# cvtv.net
KiCad netlist of a schematic drawn in EAGLE
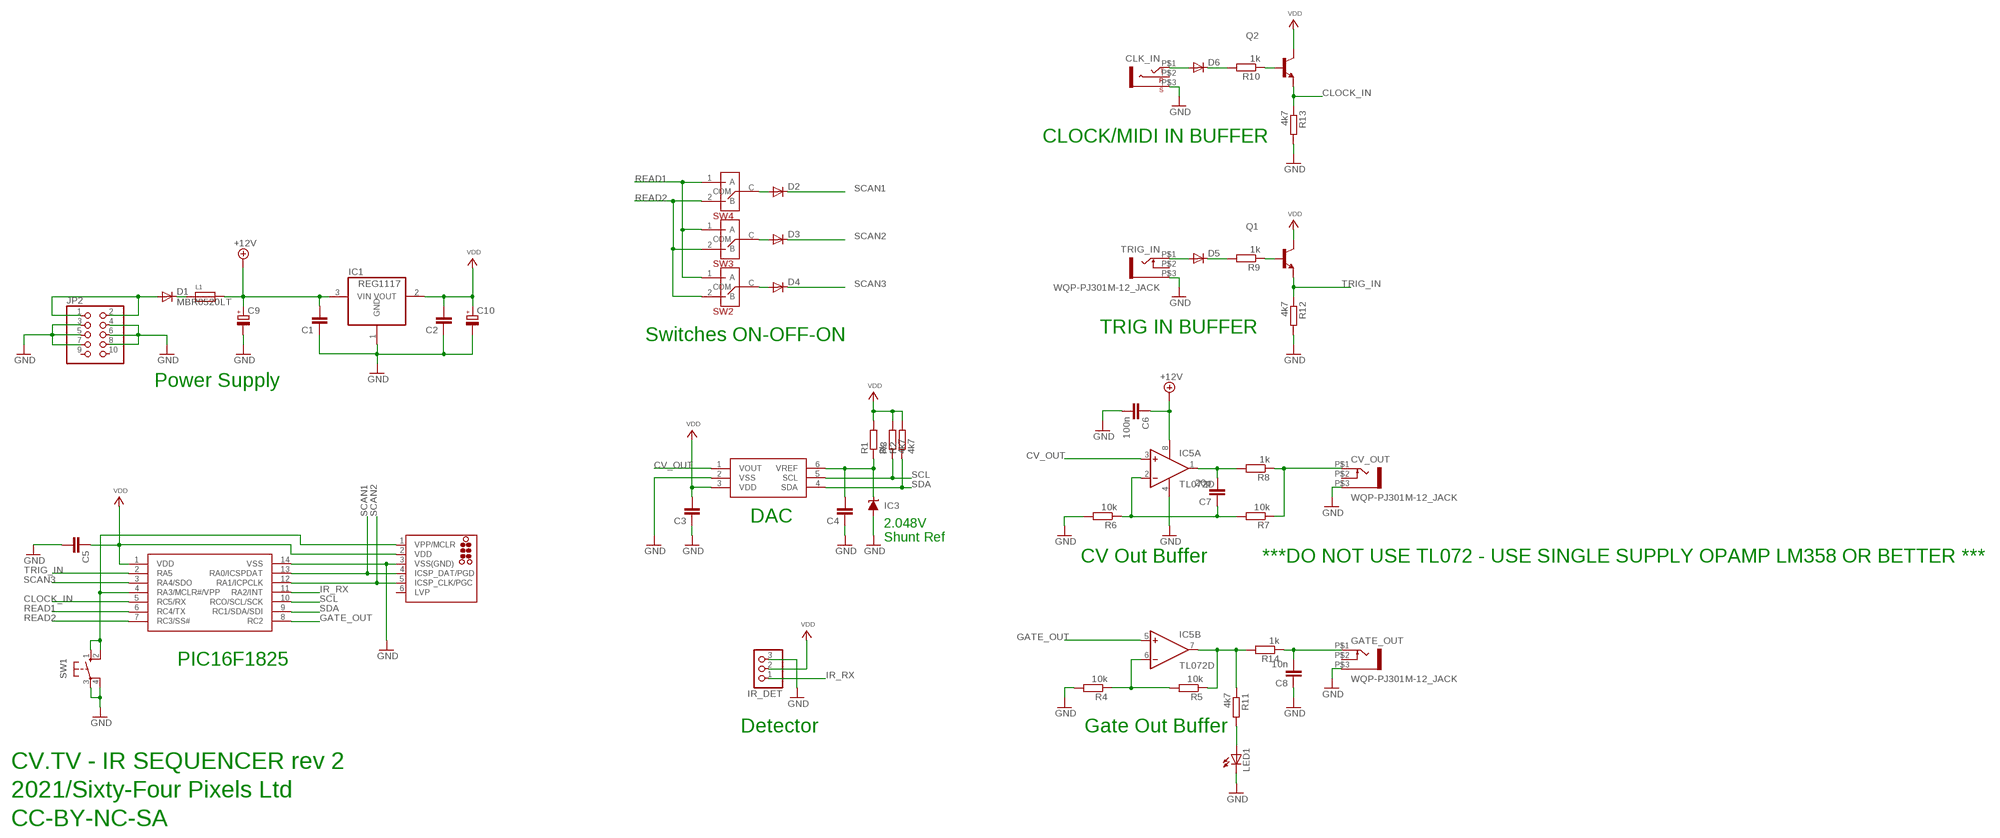
[diagram p0: schematic, sheet 1]

(export (version "E")
  (design (tool "Eeschema 10.0.6"))
  (components
    (comp (ref "C1")
      (value "C-EUC0805")
      (footprint "eagle-import:C0805")
      (libsource (lib "eagle-import") (part "C-EUC0805"))
    )
    (comp (ref "C2")
      (value "C-EUC0805")
      (footprint "eagle-import:C0805")
      (libsource (lib "eagle-import") (part "C-EUC0805"))
    )
    (comp (ref "C3")
      (value "C-EUC0805")
      (footprint "eagle-import:C0805")
      (libsource (lib "eagle-import") (part "C-EUC0805"))
    )
    (comp (ref "C4")
      (value "C-EUC0805")
      (footprint "eagle-import:C0805")
      (libsource (lib "eagle-import") (part "C-EUC0805"))
    )
    (comp (ref "C5")
      (value "C-EUC0805")
      (footprint "eagle-import:C0805")
      (libsource (lib "eagle-import") (part "C-EUC0805"))
    )
    (comp (ref "C6")
      (value "100n")
      (footprint "eagle-import:C0805")
      (libsource (lib "eagle-import") (part "C-EUC0805"))
    )
    (comp (ref "C7")
      (value "20p")
      (footprint "eagle-import:C0805")
      (libsource (lib "eagle-import") (part "C-EUC0805"))
    )
    (comp (ref "C8")
      (value "10n")
      (footprint "eagle-import:C0805")
      (libsource (lib "eagle-import") (part "C-EUC0805"))
    )
    (comp (ref "C9")
      (value "CPOL-EUE2-5")
      (footprint "eagle-import:E2-5")
      (libsource (lib "eagle-import") (part "CPOL-EUE2-5"))
    )
    (comp (ref "C10")
      (value "CPOL-EUE2-5")
      (footprint "eagle-import:E2-5")
      (libsource (lib "eagle-import") (part "CPOL-EUE2-5"))
    )
    (comp (ref "CLK_IN")
      (value "THONKICONN_STEREO")
      (footprint "eagle-import:WQP-PJ301M-ST")
      (libsource (lib "eagle-import") (part "THONKICONN_STEREO"))
    )
    (comp (ref "CV_OUT")
      (value "WQP-PJ301M-12_JACK")
      (footprint "eagle-import:WQP-PJ301M-12_JACK")
      (libsource (lib "eagle-import") (part "WQP-PJ301M-12_JACK"))
    )
    (comp (ref "D1")
      (value "MBR0520LT")
      (footprint "eagle-import:SOD123")
      (libsource (lib "eagle-import") (part "MBR0520LT"))
    )
    (comp (ref "D2")
      (value "TS4148")
      (footprint "eagle-import:D0805")
      (libsource (lib "eagle-import") (part "TS4148"))
    )
    (comp (ref "D3")
      (value "TS4148")
      (footprint "eagle-import:D0805")
      (libsource (lib "eagle-import") (part "TS4148"))
    )
    (comp (ref "D4")
      (value "TS4148")
      (footprint "eagle-import:D0805")
      (libsource (lib "eagle-import") (part "TS4148"))
    )
    (comp (ref "D5")
      (value "TS4148")
      (footprint "eagle-import:D0805")
      (libsource (lib "eagle-import") (part "TS4148"))
    )
    (comp (ref "D6")
      (value "TS4148")
      (footprint "eagle-import:D0805")
      (libsource (lib "eagle-import") (part "TS4148"))
    )
    (comp (ref "GATE_OUT")
      (value "WQP-PJ301M-12_JACK")
      (footprint "eagle-import:WQP-PJ301M-12_JACK")
      (libsource (lib "eagle-import") (part "WQP-PJ301M-12_JACK"))
    )
    (comp (ref "IC1")
      (value "REG1117")
      (footprint "eagle-import:SOT223")
      (libsource (lib "eagle-import") (part "REG1117"))
    )
    (comp (ref "IC2")
      (value "PIC16F1825SO14")
      (footprint "eagle-import:SO14")
      (libsource (lib "eagle-import") (part "PIC16F1825SO14"))
    )
    (comp (ref "IC3")
      (value "LM4041A12DBZ")
      (footprint "eagle-import:DBZ_R-PDSO-G3")
      (fields (field (name "MPN") "LM4041A12IDBZR"))
      (libsource (lib "eagle-import") (part "LM4041DBZA12"))
    )
    (comp (ref "IC4")
      (value "MCP4726")
      (footprint "eagle-import:SOT23-6")
      (libsource (lib "eagle-import") (part "MCP4726"))
    )
    (comp (ref "IC5")
      (value "TL072D")
      (footprint "eagle-import:SO08")
      (libsource (lib "eagle-import") (part "TL072D"))
    )
    (comp (ref "ICSP")
      (value "TC2030-MCP-NL")
      (footprint "eagle-import:TC2030-MCP-NL")
      (libsource (lib "eagle-import") (part "TC2030-MCP-NL"))
    )
    (comp (ref "IR_DET")
      (value "PINHD-1X3")
      (footprint "eagle-import:1X03")
      (libsource (lib "eagle-import") (part "PINHD-1X3"))
    )
    (comp (ref "JP2")
      (value "PINHD-2X5")
      (footprint "eagle-import:2X05")
      (libsource (lib "eagle-import") (part "PINHD-2X5"))
    )
    (comp (ref "L1")
      (value "FERRITE")
      (footprint "eagle-import:0603")
      (libsource (lib "eagle-import") (part "FERRITE"))
    )
    (comp (ref "LED1")
      (value "LED3MM")
      (footprint "eagle-import:LED3MM")
      (libsource (lib "eagle-import") (part "LED3MM"))
    )
    (comp (ref "Q1")
      (value "MMBT3904LT1-NPN-SOT23-BEC")
      (footprint "eagle-import:SOT23-BEC")
      (libsource (lib "eagle-import") (part "-NPN-SOT23-BECMMBT3904LT1"))
    )
    (comp (ref "Q2")
      (value "MMBT3904LT1-NPN-SOT23-BEC")
      (footprint "eagle-import:SOT23-BEC")
      (libsource (lib "eagle-import") (part "-NPN-SOT23-BECMMBT3904LT1"))
    )
    (comp (ref "R1")
      (value "3k")
      (footprint "eagle-import:R0805")
      (libsource (lib "eagle-import") (part "R-EU_R0805"))
    )
    (comp (ref "R2")
      (value "4k7")
      (footprint "eagle-import:R0805")
      (libsource (lib "eagle-import") (part "R-EU_R0805"))
    )
    (comp (ref "R3")
      (value "4k7")
      (footprint "eagle-import:R0805")
      (libsource (lib "eagle-import") (part "R-EU_R0805"))
    )
    (comp (ref "R4")
      (value "10k")
      (footprint "eagle-import:R0805")
      (libsource (lib "eagle-import") (part "R-EU_R0805"))
    )
    (comp (ref "R5")
      (value "10k")
      (footprint "eagle-import:R0805")
      (libsource (lib "eagle-import") (part "R-EU_R0805"))
    )
    (comp (ref "R6")
      (value "10k")
      (footprint "eagle-import:R0805")
      (libsource (lib "eagle-import") (part "R-EU_R0805"))
    )
    (comp (ref "R7")
      (value "10k")
      (footprint "eagle-import:R0805")
      (libsource (lib "eagle-import") (part "R-EU_R0805"))
    )
    (comp (ref "R8")
      (value "1k")
      (footprint "eagle-import:R0805")
      (libsource (lib "eagle-import") (part "R-EU_R0805"))
    )
    (comp (ref "R9")
      (value "1k")
      (footprint "eagle-import:R0805")
      (libsource (lib "eagle-import") (part "R-EU_R0805"))
    )
    (comp (ref "R10")
      (value "1k")
      (footprint "eagle-import:R0805")
      (libsource (lib "eagle-import") (part "R-EU_R0805"))
    )
    (comp (ref "R11")
      (value "4k7")
      (footprint "eagle-import:R0805")
      (libsource (lib "eagle-import") (part "R-EU_R0805"))
    )
    (comp (ref "R12")
      (value "4k7")
      (footprint "eagle-import:R0805")
      (libsource (lib "eagle-import") (part "R-EU_R0805"))
    )
    (comp (ref "R13")
      (value "4k7")
      (footprint "eagle-import:R0805")
      (libsource (lib "eagle-import") (part "R-EU_R0805"))
    )
    (comp (ref "R14")
      (value "1k")
      (footprint "eagle-import:R0805")
      (libsource (lib "eagle-import") (part "R-EU_R0805"))
    )
    (comp (ref "SW1")
      (value "10-XX")
      (footprint "eagle-import:B3F-10XX")
      (fields (field (name "MPN") "B3F-1000"))
      (libsource (lib "eagle-import") (part "10-XX"))
    )
    (comp (ref "SW2")
      (value "MICRO-SPDT")
      (footprint "eagle-import:MICRO-SPDT")
      (libsource (lib "eagle-import") (part "MICRO-SPDT"))
    )
    (comp (ref "SW3")
      (value "MICRO-SPDT")
      (footprint "eagle-import:MICRO-SPDT")
      (libsource (lib "eagle-import") (part "MICRO-SPDT"))
    )
    (comp (ref "SW4")
      (value "MICRO-SPDT")
      (footprint "eagle-import:MICRO-SPDT")
      (libsource (lib "eagle-import") (part "MICRO-SPDT"))
    )
    (comp (ref "TRIG_IN")
      (value "WQP-PJ301M-12_JACK")
      (footprint "eagle-import:WQP-PJ301M-12_JACK")
      (libsource (lib "eagle-import") (part "WQP-PJ301M-12_JACK"))
    )
  )
  (nets
    (net (code "1") (name "+12V") (class "Default")
      (node (ref "C1") (pin "2") (pinfunction "2_2") (pintype "passive"))
      (node (ref "C6") (pin "1") (pinfunction "1_1") (pintype "passive"))
      (node (ref "C9") (pin "+") (pinfunction "+_+") (pintype "passive"))
      (node (ref "IC1") (pin "3") (pinfunction "VIN_3") (pintype "input"))
      (node (ref "IC5") (pin "8") (pinfunction "V+_8") (pintype "power_in"))
      (node (ref "L1") (pin "2") (pinfunction "P$2_2") (pintype "bidirectional"))
    )
    (net (code "2") (name "/CLOCK_IN") (class "Default")
      (node (ref "IC2") (pin "5") (pinfunction "RC5/RX_5") (pintype "bidirectional"))
      (node (ref "Q2") (pin "E") (pinfunction "E_E") (pintype "passive"))
      (node (ref "R13") (pin "1") (pinfunction "1_1") (pintype "passive"))
    )
    (net (code "3") (name "/CV_OUT") (class "Default")
      (node (ref "IC4") (pin "1") (pinfunction "VOUT_1") (pintype "output"))
      (node (ref "IC5") (pin "3") (pinfunction "+IN_3") (pintype "input"))
    )
    (net (code "4") (name "/GATE_OUT") (class "Default")
      (node (ref "IC2") (pin "8") (pinfunction "RC2_8") (pintype "bidirectional"))
      (node (ref "IC5") (pin "5") (pinfunction "+IN_5") (pintype "input"))
    )
    (net (code "5") (name "/IR_RX") (class "Default")
      (node (ref "IC2") (pin "11") (pinfunction "RA2/INT_11") (pintype "bidirectional"))
      (node (ref "IR_DET") (pin "1") (pinfunction "1_1") (pintype "passive"))
    )
    (net (code "6") (name "/READ1") (class "Default")
      (node (ref "IC2") (pin "6") (pinfunction "RC4/TX_6") (pintype "bidirectional"))
      (node (ref "SW2") (pin "1") (pinfunction "A_1") (pintype "bidirectional"))
      (node (ref "SW3") (pin "1") (pinfunction "A_1") (pintype "bidirectional"))
      (node (ref "SW4") (pin "1") (pinfunction "A_1") (pintype "bidirectional"))
    )
    (net (code "7") (name "/READ2") (class "Default")
      (node (ref "IC2") (pin "7") (pinfunction "RC3/SS#_7") (pintype "bidirectional"))
      (node (ref "SW2") (pin "2") (pinfunction "B_2") (pintype "bidirectional"))
      (node (ref "SW3") (pin "2") (pinfunction "B_2") (pintype "bidirectional"))
      (node (ref "SW4") (pin "2") (pinfunction "B_2") (pintype "bidirectional"))
    )
    (net (code "8") (name "/SCAN1") (class "Default")
      (node (ref "D2") (pin "K") (pinfunction "C_K") (pintype "passive"))
      (node (ref "IC2") (pin "13") (pinfunction "RA0/ICSPDAT_13") (pintype "bidirectional"))
      (node (ref "ICSP") (pin "4") (pinfunction "ICSP_DAT/PGD_4") (pintype "bidirectional"))
    )
    (net (code "9") (name "/SCAN2") (class "Default")
      (node (ref "D3") (pin "K") (pinfunction "C_K") (pintype "passive"))
      (node (ref "IC2") (pin "12") (pinfunction "RA1/ICPCLK_12") (pintype "bidirectional"))
      (node (ref "ICSP") (pin "5") (pinfunction "ICSP_CLK/PGC_5") (pintype "output"))
    )
    (net (code "10") (name "/SCAN3") (class "Default")
      (node (ref "D4") (pin "K") (pinfunction "C_K") (pintype "passive"))
      (node (ref "IC2") (pin "3") (pinfunction "RA4/SDO_3") (pintype "bidirectional"))
    )
    (net (code "11") (name "/SCL") (class "Default")
      (node (ref "IC2") (pin "10") (pinfunction "RCO/SCL/SCK_10") (pintype "bidirectional"))
      (node (ref "IC4") (pin "5") (pinfunction "SCL_5") (pintype "bidirectional"))
      (node (ref "R3") (pin "1") (pinfunction "1_1") (pintype "passive"))
    )
    (net (code "12") (name "/SDA") (class "Default")
      (node (ref "IC2") (pin "9") (pinfunction "RC1/SDA/SDI_9") (pintype "bidirectional"))
      (node (ref "IC4") (pin "4") (pinfunction "SDA_4") (pintype "bidirectional"))
      (node (ref "R2") (pin "1") (pinfunction "1_1") (pintype "passive"))
    )
    (net (code "13") (name "/TRIG_IN") (class "Default")
      (node (ref "IC2") (pin "2") (pinfunction "RA5_2") (pintype "bidirectional"))
      (node (ref "Q1") (pin "E") (pinfunction "E_E") (pintype "passive"))
      (node (ref "R12") (pin "1") (pinfunction "1_1") (pintype "passive"))
    )
    (net (code "14") (name "GND") (class "Default")
      (node (ref "C1") (pin "1") (pinfunction "1_1") (pintype "passive"))
      (node (ref "C10") (pin "-") (pinfunction "-_-") (pintype "passive"))
      (node (ref "C2") (pin "1") (pinfunction "1_1") (pintype "passive"))
      (node (ref "C3") (pin "1") (pinfunction "1_1") (pintype "passive"))
      (node (ref "C4") (pin "1") (pinfunction "1_1") (pintype "passive"))
      (node (ref "C5") (pin "2") (pinfunction "2_2") (pintype "passive"))
      (node (ref "C6") (pin "2") (pinfunction "2_2") (pintype "passive"))
      (node (ref "C8") (pin "1") (pinfunction "1_1") (pintype "passive"))
      (node (ref "C9") (pin "-") (pinfunction "-_-") (pintype "passive"))
      (node (ref "CLK_IN") (pin "P$3") (pinfunction "S_P$3") (pintype "passive"))
      (node (ref "CV_OUT") (pin "P$3") (pinfunction "1_P$3") (pintype "passive"))
      (node (ref "GATE_OUT") (pin "P$3") (pinfunction "1_P$3") (pintype "passive"))
      (node (ref "IC1") (pin "1") (pinfunction "GND_1") (pintype "power_in"))
      (node (ref "IC2") (pin "14") (pinfunction "VSS_14") (pintype "power_in"))
      (node (ref "IC3") (pin "2") (pinfunction "A_2") (pintype "passive"))
      (node (ref "IC4") (pin "2") (pinfunction "VSS_2") (pintype "power_in"))
      (node (ref "IC5") (pin "4") (pinfunction "V-_4") (pintype "power_in"))
      (node (ref "ICSP") (pin "3") (pinfunction "VSS(GND)_3") (pintype "power_in"))
      (node (ref "IR_DET") (pin "3") (pinfunction "3_3") (pintype "passive"))
      (node (ref "JP2") (pin "3") (pinfunction "3_3") (pintype "passive"))
      (node (ref "JP2") (pin "4") (pinfunction "4_4") (pintype "passive"))
      (node (ref "JP2") (pin "5") (pinfunction "5_5") (pintype "passive"))
      (node (ref "JP2") (pin "6") (pinfunction "6_6") (pintype "passive"))
      (node (ref "JP2") (pin "7") (pinfunction "7_7") (pintype "passive"))
      (node (ref "JP2") (pin "8") (pinfunction "8_8") (pintype "passive"))
      (node (ref "LED1") (pin "K") (pinfunction "C_K") (pintype "passive"))
      (node (ref "R12") (pin "2") (pinfunction "2_2") (pintype "passive"))
      (node (ref "R13") (pin "2") (pinfunction "2_2") (pintype "passive"))
      (node (ref "R4") (pin "2") (pinfunction "2_2") (pintype "passive"))
      (node (ref "R6") (pin "2") (pinfunction "2_2") (pintype "passive"))
      (node (ref "SW1") (pin "3") (pinfunction "P_3") (pintype "passive"))
      (node (ref "SW1") (pin "4") (pinfunction "P1_4") (pintype "passive"))
      (node (ref "TRIG_IN") (pin "P$3") (pinfunction "1_P$3") (pintype "passive"))
    )
    (net (code "15") (name "Net-(CLK_IN-T)") (class "Default")
      (node (ref "CLK_IN") (pin "P$1") (pinfunction "T_P$1") (pintype "passive"))
      (node (ref "D6") (pin "A") (pinfunction "A_A") (pintype "passive"))
    )
    (net (code "16") (name "Net-(CV_OUT-2)") (class "Default")
      (node (ref "CV_OUT") (pin "P$1") (pinfunction "2_P$1") (pintype "passive"))
      (node (ref "R7") (pin "1") (pinfunction "1_1") (pintype "passive"))
      (node (ref "R8") (pin "1") (pinfunction "1_1") (pintype "passive"))
    )
    (net (code "17") (name "Net-(D1-PadA)") (class "Default")
      (node (ref "D1") (pin "A") (pinfunction "A_A") (pintype "passive"))
      (node (ref "JP2") (pin "1") (pinfunction "1_1") (pintype "passive"))
      (node (ref "JP2") (pin "2") (pinfunction "2_2") (pintype "passive"))
    )
    (net (code "18") (name "Net-(D5-C)") (class "Default")
      (node (ref "D5") (pin "K") (pinfunction "C_K") (pintype "passive"))
      (node (ref "R9") (pin "2") (pinfunction "2_2") (pintype "passive"))
    )
    (net (code "19") (name "Net-(D6-C)") (class "Default")
      (node (ref "D6") (pin "K") (pinfunction "C_K") (pintype "passive"))
      (node (ref "R10") (pin "2") (pinfunction "2_2") (pintype "passive"))
    )
    (net (code "20") (name "Net-(GATE_OUT-2)") (class "Default")
      (node (ref "C8") (pin "2") (pinfunction "2_2") (pintype "passive"))
      (node (ref "GATE_OUT") (pin "P$1") (pinfunction "2_P$1") (pintype "passive"))
      (node (ref "R14") (pin "1") (pinfunction "1_1") (pintype "passive"))
    )
    (net (code "21") (name "Net-(IC2-RA3{slash}MCLR#{slash}VPP)") (class "Default")
      (node (ref "IC2") (pin "4") (pinfunction "RA3/MCLR#/VPP_4") (pintype "input"))
      (node (ref "ICSP") (pin "1") (pinfunction "VPP/MCLR_1") (pintype "passive"))
      (node (ref "SW1") (pin "1") (pinfunction "S_1") (pintype "passive"))
      (node (ref "SW1") (pin "2") (pinfunction "S1_2") (pintype "passive"))
    )
    (net (code "22") (name "Net-(IC3-C)") (class "Default")
      (node (ref "C4") (pin "2") (pinfunction "2_2") (pintype "passive"))
      (node (ref "IC3") (pin "1") (pinfunction "C_1") (pintype "passive"))
      (node (ref "IC4") (pin "6") (pinfunction "VREF_6") (pintype "input"))
      (node (ref "R1") (pin "1") (pinfunction "1_1") (pintype "passive"))
    )
    (net (code "23") (name "Net-(IC5A--IN)") (class "Default")
      (node (ref "C7") (pin "1") (pinfunction "1_1") (pintype "passive"))
      (node (ref "IC5") (pin "2") (pinfunction "-IN_2") (pintype "input"))
      (node (ref "R6") (pin "1") (pinfunction "1_1") (pintype "passive"))
      (node (ref "R7") (pin "2") (pinfunction "2_2") (pintype "passive"))
    )
    (net (code "24") (name "Net-(IC5A-OUT)") (class "Default")
      (node (ref "C7") (pin "2") (pinfunction "2_2") (pintype "passive"))
      (node (ref "IC5") (pin "1") (pinfunction "OUT_1") (pintype "output"))
      (node (ref "R8") (pin "2") (pinfunction "2_2") (pintype "passive"))
    )
    (net (code "25") (name "Net-(IC5B--IN)") (class "Default")
      (node (ref "IC5") (pin "6") (pinfunction "-IN_6") (pintype "input"))
      (node (ref "R4") (pin "1") (pinfunction "1_1") (pintype "passive"))
      (node (ref "R5") (pin "2") (pinfunction "2_2") (pintype "passive"))
    )
    (net (code "26") (name "Net-(IC5B-OUT)") (class "Default")
      (node (ref "IC5") (pin "7") (pinfunction "OUT_7") (pintype "output"))
      (node (ref "R11") (pin "1") (pinfunction "1_1") (pintype "passive"))
      (node (ref "R14") (pin "2") (pinfunction "2_2") (pintype "passive"))
      (node (ref "R5") (pin "1") (pinfunction "1_1") (pintype "passive"))
    )
    (net (code "27") (name "Net-(L1-P$1)") (class "Default")
      (node (ref "D1") (pin "C") (pinfunction "C_C") (pintype "passive"))
      (node (ref "L1") (pin "1") (pinfunction "P$1_1") (pintype "bidirectional"))
    )
    (net (code "28") (name "Net-(LED1-PadA)") (class "Default")
      (node (ref "LED1") (pin "A") (pinfunction "A_A") (pintype "passive"))
      (node (ref "R11") (pin "2") (pinfunction "2_2") (pintype "passive"))
    )
    (net (code "29") (name "Net-(Q1-PadB)") (class "Default")
      (node (ref "Q1") (pin "B") (pinfunction "B_B") (pintype "passive"))
      (node (ref "R9") (pin "1") (pinfunction "1_1") (pintype "passive"))
    )
    (net (code "30") (name "Net-(Q2-PadB)") (class "Default")
      (node (ref "Q2") (pin "B") (pinfunction "B_B") (pintype "passive"))
      (node (ref "R10") (pin "1") (pinfunction "1_1") (pintype "passive"))
    )
    (net (code "31") (name "Net-(SW2-COM)") (class "Default")
      (node (ref "D4") (pin "A") (pinfunction "A_A") (pintype "passive"))
      (node (ref "SW2") (pin "C") (pinfunction "COM_C") (pintype "bidirectional"))
    )
    (net (code "32") (name "Net-(SW3-COM)") (class "Default")
      (node (ref "D3") (pin "A") (pinfunction "A_A") (pintype "passive"))
      (node (ref "SW3") (pin "C") (pinfunction "COM_C") (pintype "bidirectional"))
    )
    (net (code "33") (name "Net-(SW4-COM)") (class "Default")
      (node (ref "D2") (pin "A") (pinfunction "A_A") (pintype "passive"))
      (node (ref "SW4") (pin "C") (pinfunction "COM_C") (pintype "bidirectional"))
    )
    (net (code "34") (name "Net-(TRIG_IN-2)") (class "Default")
      (node (ref "D5") (pin "A") (pinfunction "A_A") (pintype "passive"))
      (node (ref "TRIG_IN") (pin "P$1") (pinfunction "2_P$1") (pintype "passive"))
    )
    (net (code "35") (name "VDD") (class "Default")
      (node (ref "C10") (pin "+") (pinfunction "+_+") (pintype "passive"))
      (node (ref "C2") (pin "2") (pinfunction "2_2") (pintype "passive"))
      (node (ref "C3") (pin "2") (pinfunction "2_2") (pintype "passive"))
      (node (ref "C5") (pin "1") (pinfunction "1_1") (pintype "passive"))
      (node (ref "IC1") (pin "2") (pinfunction "VOUT_2") (pintype "output"))
      (node (ref "IC2") (pin "1") (pinfunction "VDD_1") (pintype "power_in"))
      (node (ref "IC4") (pin "3") (pinfunction "VDD_3") (pintype "power_in"))
      (node (ref "ICSP") (pin "2") (pinfunction "VDD_2") (pintype "power_in"))
      (node (ref "IR_DET") (pin "2") (pinfunction "2_2") (pintype "passive"))
      (node (ref "Q1") (pin "C") (pinfunction "C_C") (pintype "passive"))
      (node (ref "Q2") (pin "C") (pinfunction "C_C") (pintype "passive"))
      (node (ref "R1") (pin "2") (pinfunction "2_2") (pintype "passive"))
      (node (ref "R2") (pin "2") (pinfunction "2_2") (pintype "passive"))
      (node (ref "R3") (pin "2") (pinfunction "2_2") (pintype "passive"))
    )
    (net (code "36") (name "unconnected-(CLK_IN-R-PadP$2)") (class "Default")
      (node (ref "CLK_IN") (pin "P$2") (pinfunction "R_P$2") (pintype "passive"))
    )
    (net (code "37") (name "unconnected-(CV_OUT-3-PadP$2)") (class "Default")
      (node (ref "CV_OUT") (pin "P$2") (pinfunction "3_P$2") (pintype "passive"))
    )
    (net (code "38") (name "unconnected-(GATE_OUT-3-PadP$2)") (class "Default")
      (node (ref "GATE_OUT") (pin "P$2") (pinfunction "3_P$2") (pintype "passive"))
    )
    (net (code "39") (name "unconnected-(ICSP-LVP-Pad6)") (class "Default")
      (node (ref "ICSP") (pin "6") (pinfunction "LVP_6") (pintype "bidirectional"))
    )
    (net (code "40") (name "unconnected-(JP2-Pad9)") (class "Default")
      (node (ref "JP2") (pin "9") (pinfunction "9_9") (pintype "passive"))
    )
    (net (code "41") (name "unconnected-(JP2-Pad10)") (class "Default")
      (node (ref "JP2") (pin "10") (pinfunction "10_10") (pintype "passive"))
    )
    (net (code "42") (name "unconnected-(TRIG_IN-3-PadP$2)") (class "Default")
      (node (ref "TRIG_IN") (pin "P$2") (pinfunction "3_P$2") (pintype "passive"))
    )
  )
)
